# Spatium_B_Model_Uydu_PCB_newline_2021.net
KiCad netlist of a schematic drawn in EAGLE
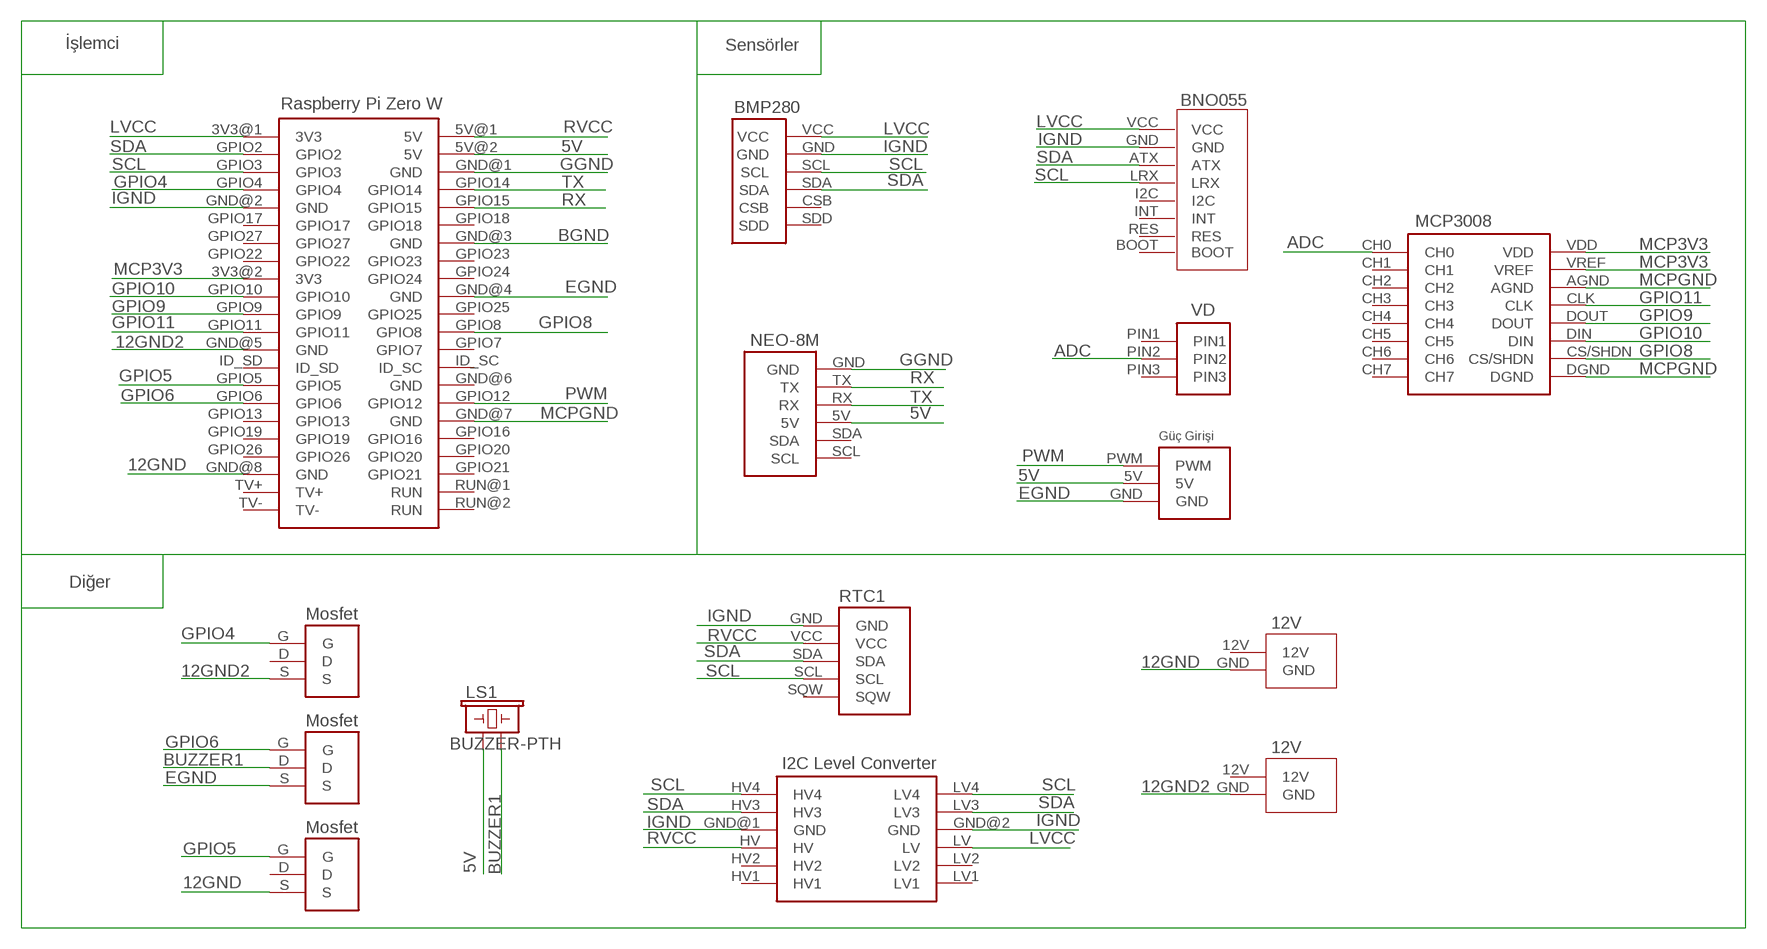
[diagram p0: schematic, sheet 1]

(export (version "E")
  (design (tool "Eeschema 10.0.6"))
  (components
    (comp (ref "BNO1")
      (value "BNO055")
      (footprint "eagle-import:BNO055")
      (libsource (lib "eagle-import") (part "BNO055"))
    )
    (comp (ref "LS1")
      (value "BUZZER-PTH")
      (footprint "eagle-import:BUZZER-12MM")
      (libsource (lib "eagle-import") (part "BUZZER-PTH"))
    )
    (comp (ref "RTC1")
      (value "PCF8523_RTC")
      (footprint "eagle-import:PCF8523_RTC")
      (libsource (lib "eagle-import") (part "PCF8523_RTC"))
    )
    (comp (ref "U$1")
      (value "RASPBERRY_ZERO_W")
      (footprint "eagle-import:RASPBERRY_ZERO_W")
      (libsource (lib "eagle-import") (part "RASPBERRY_ZERO_W"))
    )
    (comp (ref "U$2")
      (value "BMP280")
      (footprint "eagle-import:BMP280")
      (libsource (lib "eagle-import") (part "BMP280"))
    )
    (comp (ref "U$3")
      (value "I2C_LOGIC_LEVEL_CONVERTER")
      (footprint "eagle-import:I2C_LOGIC_LEVEL_CONVERTER")
      (libsource (lib "eagle-import") (part "I2C_LOGIC_LEVEL_CONVERTER"))
    )
    (comp (ref "U$4")
      (value "NEOM8N")
      (footprint "eagle-import:NEO8M")
      (libsource (lib "eagle-import") (part "NEOM8N"))
    )
    (comp (ref "U$5")
      (value "VOLTAGE_DIVIDER")
      (footprint "eagle-import:VOLTAGE_DIVIDER")
      (libsource (lib "eagle-import") (part "VOLTAGE_DIVIDER"))
    )
    (comp (ref "U$6")
      (value "MOSFET")
      (footprint "eagle-import:MOSFET")
      (libsource (lib "eagle-import") (part "MOSFET"))
    )
    (comp (ref "U$7")
      (value "Güç_GIRIS")
      (footprint "eagle-import:Güç_GIRIS")
      (libsource (lib "eagle-import") (part "Güç_GIRIS"))
    )
    (comp (ref "U$8")
      (value "MOSFET")
      (footprint "eagle-import:MOSFET")
      (libsource (lib "eagle-import") (part "MOSFET"))
    )
    (comp (ref "U$9")
      (value "MOSFET")
      (footprint "eagle-import:MOSFET")
      (libsource (lib "eagle-import") (part "MOSFET"))
    )
    (comp (ref "U$10")
      (value "12V")
      (footprint "eagle-import:12V")
      (libsource (lib "eagle-import") (part "12V"))
    )
    (comp (ref "U$11")
      (value "12V")
      (footprint "eagle-import:12V")
      (libsource (lib "eagle-import") (part "12V"))
    )
    (comp (ref "U$12")
      (value "MCP3008")
      (footprint "eagle-import:MCP3008")
      (libsource (lib "eagle-import") (part "MCP3008"))
    )
  )
  (nets
    (net (code "1") (name "/5V") (class "Default")
      (node (ref "LS1") (pin "+") (pinfunction "1_+") (pintype "passive"))
      (node (ref "U$1") (pin "5V@2") (pinfunction "5V_5V@2") (pintype "bidirectional"))
      (node (ref "U$4") (pin "5V") (pinfunction "5V_5V") (pintype "bidirectional"))
      (node (ref "U$7") (pin "5V") (pinfunction "5V_5V") (pintype "bidirectional"))
    )
    (net (code "2") (name "/12GND") (class "Default")
      (node (ref "U$1") (pin "GND@8") (pinfunction "GND_GND@8") (pintype "bidirectional"))
      (node (ref "U$10") (pin "GND") (pinfunction "GND_GND") (pintype "bidirectional"))
      (node (ref "U$6") (pin "S") (pinfunction "S_S") (pintype "bidirectional"))
    )
    (net (code "3") (name "/12GND2") (class "Default")
      (node (ref "U$1") (pin "GND@5") (pinfunction "GND_GND@5") (pintype "bidirectional"))
      (node (ref "U$11") (pin "GND") (pinfunction "GND_GND") (pintype "bidirectional"))
      (node (ref "U$9") (pin "S") (pinfunction "S_S") (pintype "bidirectional"))
    )
    (net (code "4") (name "/ADC") (class "Default")
      (node (ref "U$12") (pin "CH0") (pinfunction "CH0_CH0") (pintype "bidirectional"))
      (node (ref "U$5") (pin "PIN2") (pinfunction "PIN2_PIN2") (pintype "bidirectional"))
    )
    (net (code "5") (name "/BGND") (class "Default")
      (node (ref "U$1") (pin "GND@3") (pinfunction "GND_GND@3") (pintype "bidirectional"))
    )
    (net (code "6") (name "/BUZZER1") (class "Default")
      (node (ref "LS1") (pin "-") (pinfunction "2_-") (pintype "passive"))
      (node (ref "U$8") (pin "D") (pinfunction "D_D") (pintype "bidirectional"))
    )
    (net (code "7") (name "/EGND") (class "Default")
      (node (ref "U$1") (pin "GND@4") (pinfunction "GND_GND@4") (pintype "bidirectional"))
      (node (ref "U$7") (pin "GND") (pinfunction "GND_GND") (pintype "bidirectional"))
      (node (ref "U$8") (pin "S") (pinfunction "S_S") (pintype "bidirectional"))
    )
    (net (code "8") (name "/GGND") (class "Default")
      (node (ref "U$1") (pin "GND@1") (pinfunction "GND_GND@1") (pintype "bidirectional"))
      (node (ref "U$4") (pin "GND") (pinfunction "GND_GND") (pintype "bidirectional"))
    )
    (net (code "9") (name "/GPIO4") (class "Default")
      (node (ref "U$1") (pin "GPIO4") (pinfunction "GPIO4_GPIO4") (pintype "bidirectional"))
      (node (ref "U$9") (pin "G") (pinfunction "G_G") (pintype "bidirectional"))
    )
    (net (code "10") (name "/GPIO5") (class "Default")
      (node (ref "U$1") (pin "GPIO5") (pinfunction "GPIO5_GPIO5") (pintype "bidirectional"))
      (node (ref "U$6") (pin "G") (pinfunction "G_G") (pintype "bidirectional"))
    )
    (net (code "11") (name "/GPIO6") (class "Default")
      (node (ref "U$1") (pin "GPIO6") (pinfunction "GPIO6_GPIO6") (pintype "bidirectional"))
      (node (ref "U$8") (pin "G") (pinfunction "G_G") (pintype "bidirectional"))
    )
    (net (code "12") (name "/GPIO8") (class "Default")
      (node (ref "U$1") (pin "GPIO8") (pinfunction "GPIO8_GPIO8") (pintype "bidirectional"))
      (node (ref "U$12") (pin "CS/SHDN") (pinfunction "CS/SHDN_CS/SHDN") (pintype "bidirectional"))
    )
    (net (code "13") (name "/GPIO9") (class "Default")
      (node (ref "U$1") (pin "GPIO9") (pinfunction "GPIO9_GPIO9") (pintype "bidirectional"))
      (node (ref "U$12") (pin "DOUT") (pinfunction "DOUT_DOUT") (pintype "bidirectional"))
    )
    (net (code "14") (name "/GPIO10") (class "Default")
      (node (ref "U$1") (pin "GPIO10") (pinfunction "GPIO10_GPIO10") (pintype "bidirectional"))
      (node (ref "U$12") (pin "DIN") (pinfunction "DIN_DIN") (pintype "bidirectional"))
    )
    (net (code "15") (name "/GPIO11") (class "Default")
      (node (ref "U$1") (pin "GPIO11") (pinfunction "GPIO11_GPIO11") (pintype "bidirectional"))
      (node (ref "U$12") (pin "CLK") (pinfunction "CLK_CLK") (pintype "bidirectional"))
    )
    (net (code "16") (name "/IGND") (class "Default")
      (node (ref "BNO1") (pin "GND") (pinfunction "GND_GND") (pintype "bidirectional"))
      (node (ref "RTC1") (pin "GND") (pinfunction "GND_GND") (pintype "bidirectional"))
      (node (ref "U$1") (pin "GND@2") (pinfunction "GND_GND@2") (pintype "bidirectional"))
      (node (ref "U$2") (pin "GND") (pinfunction "GND_GND") (pintype "bidirectional"))
      (node (ref "U$3") (pin "GND@1") (pinfunction "GND_GND@1") (pintype "bidirectional"))
      (node (ref "U$3") (pin "GND@2") (pinfunction "GND_GND@2") (pintype "bidirectional"))
    )
    (net (code "17") (name "/LVCC") (class "Default")
      (node (ref "BNO1") (pin "VCC") (pinfunction "VCC_VCC") (pintype "bidirectional"))
      (node (ref "U$1") (pin "3V3@1") (pinfunction "3V3_3V3@1") (pintype "bidirectional"))
      (node (ref "U$2") (pin "VCC") (pinfunction "VCC_VCC") (pintype "bidirectional"))
      (node (ref "U$3") (pin "LV") (pinfunction "LV_LV") (pintype "bidirectional"))
    )
    (net (code "18") (name "/MCP3V3") (class "Default")
      (node (ref "U$1") (pin "3V3@2") (pinfunction "3V3_3V3@2") (pintype "bidirectional"))
      (node (ref "U$12") (pin "VDD") (pinfunction "VDD_VDD") (pintype "bidirectional"))
      (node (ref "U$12") (pin "VREF") (pinfunction "VREF_VREF") (pintype "bidirectional"))
    )
    (net (code "19") (name "/MCPGND") (class "Default")
      (node (ref "U$1") (pin "GND@7") (pinfunction "GND_GND@7") (pintype "bidirectional"))
      (node (ref "U$12") (pin "AGND") (pinfunction "AGND_AGND") (pintype "bidirectional"))
      (node (ref "U$12") (pin "DGND") (pinfunction "DGND_DGND") (pintype "bidirectional"))
    )
    (net (code "20") (name "/PWM") (class "Default")
      (node (ref "U$1") (pin "GPIO12") (pinfunction "GPIO12_GPIO12") (pintype "bidirectional"))
      (node (ref "U$7") (pin "PWM") (pinfunction "PWM_PWM") (pintype "bidirectional"))
    )
    (net (code "21") (name "/RVCC") (class "Default")
      (node (ref "RTC1") (pin "VCC") (pinfunction "VCC_VCC") (pintype "bidirectional"))
      (node (ref "U$1") (pin "5V@1") (pinfunction "5V_5V@1") (pintype "bidirectional"))
      (node (ref "U$3") (pin "HV") (pinfunction "HV_HV") (pintype "bidirectional"))
    )
    (net (code "22") (name "/RX") (class "Default")
      (node (ref "U$1") (pin "GPIO15") (pinfunction "GPIO15_GPIO15") (pintype "bidirectional"))
      (node (ref "U$4") (pin "TX") (pinfunction "TX_TX") (pintype "bidirectional"))
    )
    (net (code "23") (name "/SCL") (class "Default")
      (node (ref "BNO1") (pin "LRX") (pinfunction "LRX_LRX") (pintype "bidirectional"))
      (node (ref "RTC1") (pin "SCL") (pinfunction "SCL_SCL") (pintype "bidirectional"))
      (node (ref "U$1") (pin "GPIO3") (pinfunction "GPIO3_GPIO3") (pintype "bidirectional"))
      (node (ref "U$2") (pin "SCL") (pinfunction "SCL_SCL") (pintype "bidirectional"))
      (node (ref "U$3") (pin "HV4") (pinfunction "HV4_HV4") (pintype "bidirectional"))
      (node (ref "U$3") (pin "LV4") (pinfunction "LV4_LV4") (pintype "bidirectional"))
    )
    (net (code "24") (name "/SDA") (class "Default")
      (node (ref "BNO1") (pin "ATX") (pinfunction "ATX_ATX") (pintype "bidirectional"))
      (node (ref "RTC1") (pin "SDA") (pinfunction "SDA_SDA") (pintype "bidirectional"))
      (node (ref "U$1") (pin "GPIO2") (pinfunction "GPIO2_GPIO2") (pintype "bidirectional"))
      (node (ref "U$2") (pin "SDA") (pinfunction "SDA_SDA") (pintype "bidirectional"))
      (node (ref "U$3") (pin "HV3") (pinfunction "HV3_HV3") (pintype "bidirectional"))
      (node (ref "U$3") (pin "LV3") (pinfunction "LV3_LV3") (pintype "bidirectional"))
    )
    (net (code "25") (name "/TX") (class "Default")
      (node (ref "U$1") (pin "GPIO14") (pinfunction "GPIO14_GPIO14") (pintype "bidirectional"))
      (node (ref "U$4") (pin "RX") (pinfunction "RX_RX") (pintype "bidirectional"))
    )
    (net (code "26") (name "unconnected-(BNO1-PadBOOT)") (class "Default")
      (node (ref "BNO1") (pin "BOOT") (pinfunction "BOOT_BOOT") (pintype "bidirectional"))
    )
    (net (code "27") (name "unconnected-(BNO1-PadI2C)") (class "Default")
      (node (ref "BNO1") (pin "I2C") (pinfunction "I2C_I2C") (pintype "bidirectional"))
    )
    (net (code "28") (name "unconnected-(BNO1-PadINT)") (class "Default")
      (node (ref "BNO1") (pin "INT") (pinfunction "INT_INT") (pintype "bidirectional"))
    )
    (net (code "29") (name "unconnected-(BNO1-PadRES)") (class "Default")
      (node (ref "BNO1") (pin "RES") (pinfunction "RES_RES") (pintype "bidirectional"))
    )
    (net (code "30") (name "unconnected-(RTC1-PadSQW)") (class "Default")
      (node (ref "RTC1") (pin "SQW") (pinfunction "SQW_SQW") (pintype "bidirectional"))
    )
    (net (code "31") (name "unconnected-(U$1-GND-PadGND@6)") (class "Default")
      (node (ref "U$1") (pin "GND@6") (pinfunction "GND_GND@6") (pintype "bidirectional"))
    )
    (net (code "32") (name "unconnected-(U$1-PadGPIO7)") (class "Default")
      (node (ref "U$1") (pin "GPIO7") (pinfunction "GPIO7_GPIO7") (pintype "bidirectional"))
    )
    (net (code "33") (name "unconnected-(U$1-PadGPIO13)") (class "Default")
      (node (ref "U$1") (pin "GPIO13") (pinfunction "GPIO13_GPIO13") (pintype "bidirectional"))
    )
    (net (code "34") (name "unconnected-(U$1-PadGPIO16)") (class "Default")
      (node (ref "U$1") (pin "GPIO16") (pinfunction "GPIO16_GPIO16") (pintype "bidirectional"))
    )
    (net (code "35") (name "unconnected-(U$1-PadGPIO17)") (class "Default")
      (node (ref "U$1") (pin "GPIO17") (pinfunction "GPIO17_GPIO17") (pintype "bidirectional"))
    )
    (net (code "36") (name "unconnected-(U$1-PadGPIO18)") (class "Default")
      (node (ref "U$1") (pin "GPIO18") (pinfunction "GPIO18_GPIO18") (pintype "bidirectional"))
    )
    (net (code "37") (name "unconnected-(U$1-PadGPIO19)") (class "Default")
      (node (ref "U$1") (pin "GPIO19") (pinfunction "GPIO19_GPIO19") (pintype "bidirectional"))
    )
    (net (code "38") (name "unconnected-(U$1-PadGPIO20)") (class "Default")
      (node (ref "U$1") (pin "GPIO20") (pinfunction "GPIO20_GPIO20") (pintype "bidirectional"))
    )
    (net (code "39") (name "unconnected-(U$1-PadGPIO21)") (class "Default")
      (node (ref "U$1") (pin "GPIO21") (pinfunction "GPIO21_GPIO21") (pintype "bidirectional"))
    )
    (net (code "40") (name "unconnected-(U$1-PadGPIO22)") (class "Default")
      (node (ref "U$1") (pin "GPIO22") (pinfunction "GPIO22_GPIO22") (pintype "bidirectional"))
    )
    (net (code "41") (name "unconnected-(U$1-PadGPIO23)") (class "Default")
      (node (ref "U$1") (pin "GPIO23") (pinfunction "GPIO23_GPIO23") (pintype "bidirectional"))
    )
    (net (code "42") (name "unconnected-(U$1-PadGPIO24)") (class "Default")
      (node (ref "U$1") (pin "GPIO24") (pinfunction "GPIO24_GPIO24") (pintype "bidirectional"))
    )
    (net (code "43") (name "unconnected-(U$1-PadGPIO25)") (class "Default")
      (node (ref "U$1") (pin "GPIO25") (pinfunction "GPIO25_GPIO25") (pintype "bidirectional"))
    )
    (net (code "44") (name "unconnected-(U$1-PadGPIO26)") (class "Default")
      (node (ref "U$1") (pin "GPIO26") (pinfunction "GPIO26_GPIO26") (pintype "bidirectional"))
    )
    (net (code "45") (name "unconnected-(U$1-PadGPIO27)") (class "Default")
      (node (ref "U$1") (pin "GPIO27") (pinfunction "GPIO27_GPIO27") (pintype "bidirectional"))
    )
    (net (code "46") (name "unconnected-(U$1-PadID_SC)") (class "Default")
      (node (ref "U$1") (pin "ID_SC") (pinfunction "ID_SC_ID_SC") (pintype "bidirectional"))
    )
    (net (code "47") (name "unconnected-(U$1-PadID_SD)") (class "Default")
      (node (ref "U$1") (pin "ID_SD") (pinfunction "ID_SD_ID_SD") (pintype "bidirectional"))
    )
    (net (code "48") (name "unconnected-(U$1-PadTV+)") (class "Default")
      (node (ref "U$1") (pin "TV+") (pinfunction "TV+_TV+") (pintype "bidirectional"))
    )
    (net (code "49") (name "unconnected-(U$1-PadTV-)") (class "Default")
      (node (ref "U$1") (pin "TV-") (pinfunction "TV-_TV-") (pintype "bidirectional"))
    )
    (net (code "50") (name "unconnected-(U$1-RUN-PadRUN@1)") (class "Default")
      (node (ref "U$1") (pin "RUN@1") (pinfunction "RUN_RUN@1") (pintype "bidirectional"))
    )
    (net (code "51") (name "unconnected-(U$1-RUN-PadRUN@2)") (class "Default")
      (node (ref "U$1") (pin "RUN@2") (pinfunction "RUN_RUN@2") (pintype "bidirectional"))
    )
    (net (code "52") (name "unconnected-(U$2-PadCSB)") (class "Default")
      (node (ref "U$2") (pin "CSB") (pinfunction "CSB_CSB") (pintype "bidirectional"))
    )
    (net (code "53") (name "unconnected-(U$2-PadSDD)") (class "Default")
      (node (ref "U$2") (pin "SDD") (pinfunction "SDD_SDD") (pintype "bidirectional"))
    )
    (net (code "54") (name "unconnected-(U$3-PadHV1)") (class "Default")
      (node (ref "U$3") (pin "HV1") (pinfunction "HV1_HV1") (pintype "bidirectional"))
    )
    (net (code "55") (name "unconnected-(U$3-PadHV2)") (class "Default")
      (node (ref "U$3") (pin "HV2") (pinfunction "HV2_HV2") (pintype "bidirectional"))
    )
    (net (code "56") (name "unconnected-(U$3-PadLV1)") (class "Default")
      (node (ref "U$3") (pin "LV1") (pinfunction "LV1_LV1") (pintype "bidirectional"))
    )
    (net (code "57") (name "unconnected-(U$3-PadLV2)") (class "Default")
      (node (ref "U$3") (pin "LV2") (pinfunction "LV2_LV2") (pintype "bidirectional"))
    )
    (net (code "58") (name "unconnected-(U$4-PadSCL)") (class "Default")
      (node (ref "U$4") (pin "SCL") (pinfunction "SCL_SCL") (pintype "bidirectional"))
    )
    (net (code "59") (name "unconnected-(U$4-PadSDA)") (class "Default")
      (node (ref "U$4") (pin "SDA") (pinfunction "SDA_SDA") (pintype "bidirectional"))
    )
    (net (code "60") (name "unconnected-(U$5-PadPIN1)") (class "Default")
      (node (ref "U$5") (pin "PIN1") (pinfunction "PIN1_PIN1") (pintype "bidirectional"))
    )
    (net (code "61") (name "unconnected-(U$5-PadPIN3)") (class "Default")
      (node (ref "U$5") (pin "PIN3") (pinfunction "PIN3_PIN3") (pintype "bidirectional"))
    )
    (net (code "62") (name "unconnected-(U$6-PadD)") (class "Default")
      (node (ref "U$6") (pin "D") (pinfunction "D_D") (pintype "bidirectional"))
    )
    (net (code "63") (name "unconnected-(U$9-PadD)") (class "Default")
      (node (ref "U$9") (pin "D") (pinfunction "D_D") (pintype "bidirectional"))
    )
    (net (code "64") (name "unconnected-(U$10-Pad12V)") (class "Default")
      (node (ref "U$10") (pin "12V") (pinfunction "12V_12V") (pintype "bidirectional"))
    )
    (net (code "65") (name "unconnected-(U$11-Pad12V)") (class "Default")
      (node (ref "U$11") (pin "12V") (pinfunction "12V_12V") (pintype "bidirectional"))
    )
    (net (code "66") (name "unconnected-(U$12-PadCH1)") (class "Default")
      (node (ref "U$12") (pin "CH1") (pinfunction "CH1_CH1") (pintype "bidirectional"))
    )
    (net (code "67") (name "unconnected-(U$12-PadCH2)") (class "Default")
      (node (ref "U$12") (pin "CH2") (pinfunction "CH2_CH2") (pintype "bidirectional"))
    )
    (net (code "68") (name "unconnected-(U$12-PadCH3)") (class "Default")
      (node (ref "U$12") (pin "CH3") (pinfunction "CH3_CH3") (pintype "bidirectional"))
    )
    (net (code "69") (name "unconnected-(U$12-PadCH4)") (class "Default")
      (node (ref "U$12") (pin "CH4") (pinfunction "CH4_CH4") (pintype "bidirectional"))
    )
    (net (code "70") (name "unconnected-(U$12-PadCH5)") (class "Default")
      (node (ref "U$12") (pin "CH5") (pinfunction "CH5_CH5") (pintype "bidirectional"))
    )
    (net (code "71") (name "unconnected-(U$12-PadCH6)") (class "Default")
      (node (ref "U$12") (pin "CH6") (pinfunction "CH6_CH6") (pintype "bidirectional"))
    )
    (net (code "72") (name "unconnected-(U$12-PadCH7)") (class "Default")
      (node (ref "U$12") (pin "CH7") (pinfunction "CH7_CH7") (pintype "bidirectional"))
    )
  )
)
